# DIP_REFLOW_v1.net
KiCad netlist of a schematic drawn in EAGLE
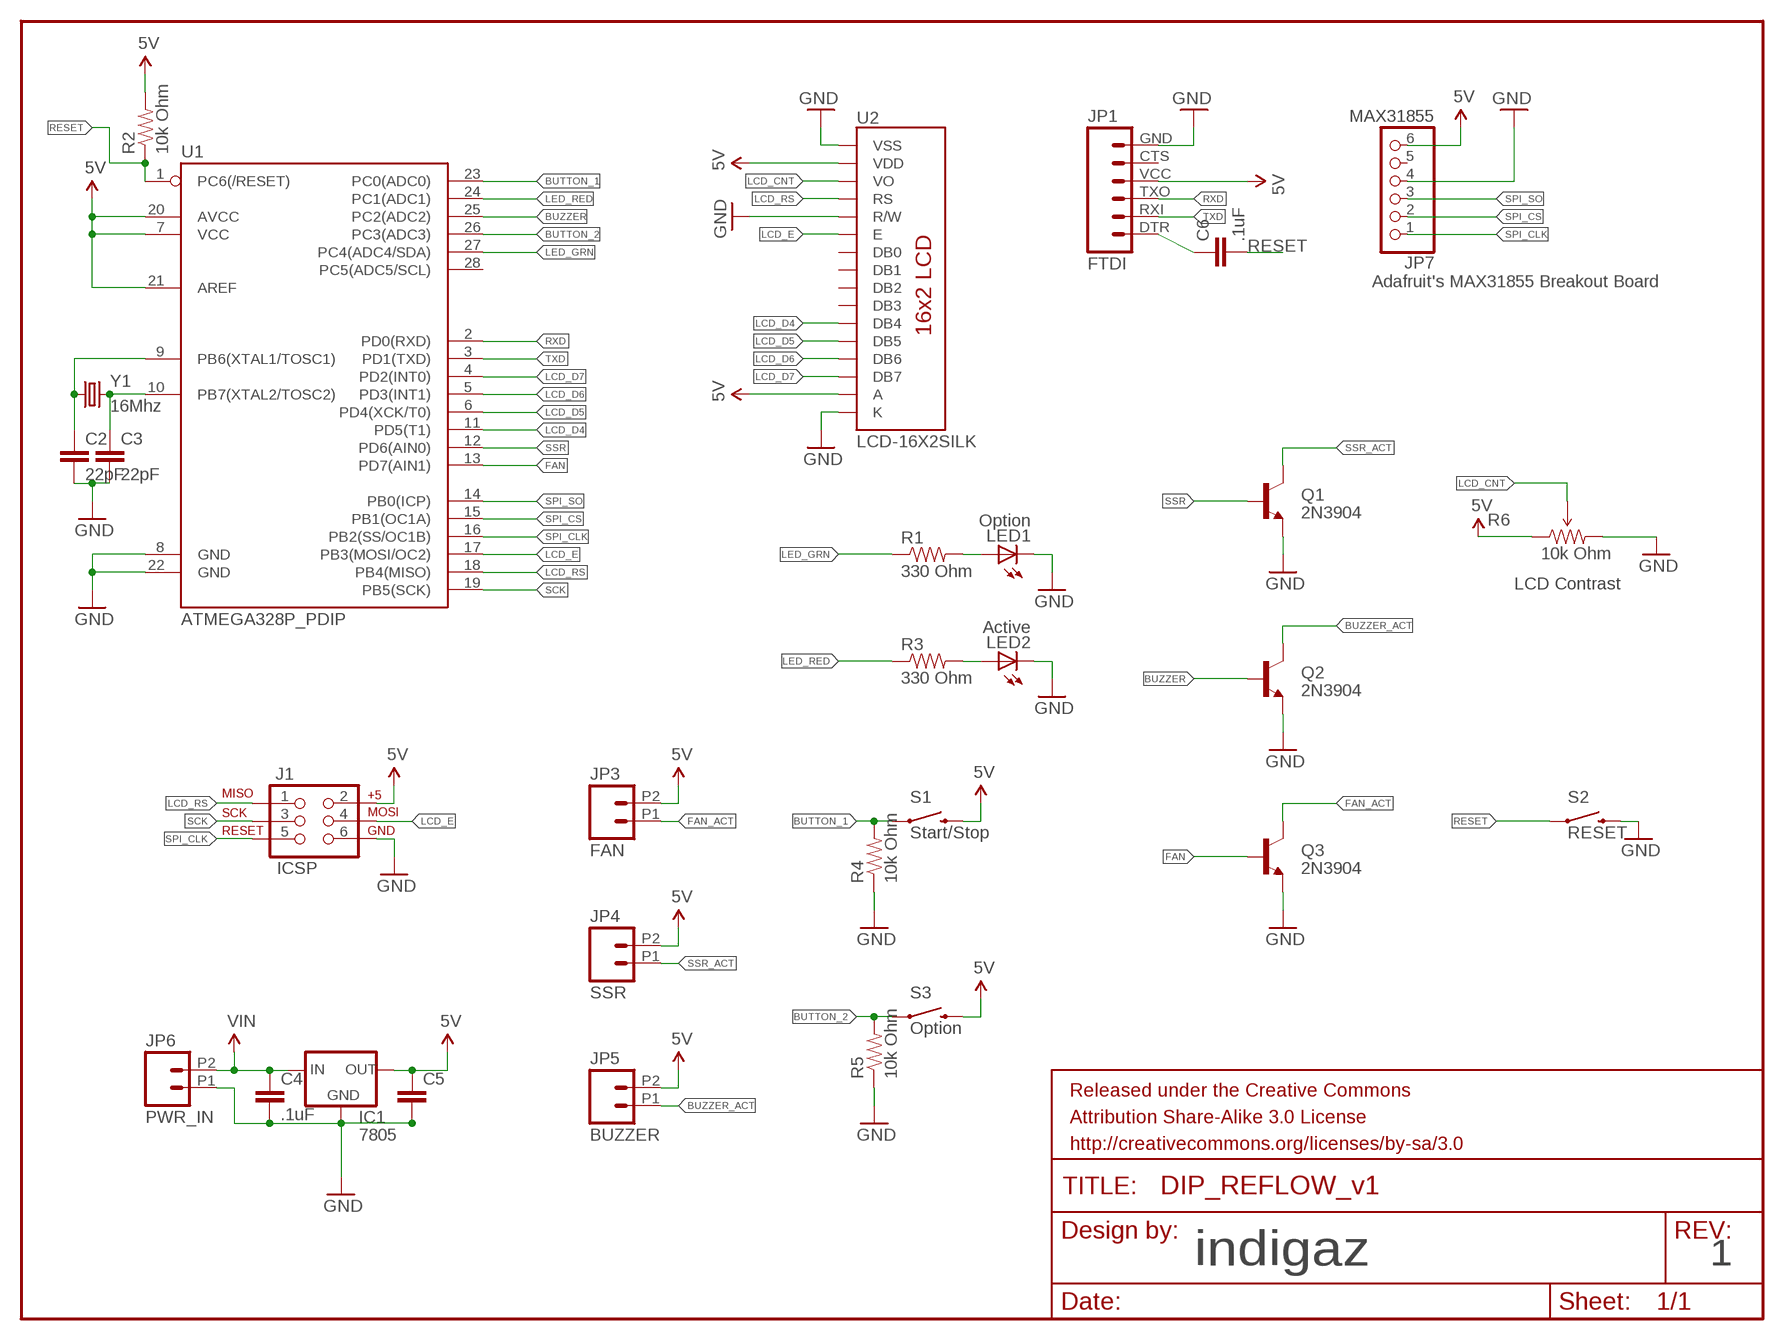
[diagram p0: schematic, sheet 1]

(export (version "E")
  (design (tool "Eeschema 10.0.6"))
  (components
    (comp (ref "C2")
      (value "22pF")
      (footprint "eagle-import:CAP-PTH-5MM")
      (libsource (lib "eagle-import") (part "CAPPTH1"))
    )
    (comp (ref "C3")
      (value "22pF")
      (footprint "eagle-import:CAP-PTH-5MM")
      (libsource (lib "eagle-import") (part "CAPPTH1"))
    )
    (comp (ref "C4")
      (value ".1uF")
      (footprint "eagle-import:CAP-PTH-5MM")
      (libsource (lib "eagle-import") (part "CAPPTH1"))
    )
    (comp (ref "C5")
      (value "CAPPTH1")
      (footprint "eagle-import:CAP-PTH-5MM")
      (libsource (lib "eagle-import") (part "CAPPTH1"))
    )
    (comp (ref "C6")
      (value ".1uF")
      (footprint "eagle-import:CAP-PTH-5MM")
      (libsource (lib "eagle-import") (part "CAPPTH1"))
    )
    (comp (ref "FRAME1")
      (value "FRAME-LETTER")
      (footprint "eagle-import:CREATIVE_COMMONS")
      (libsource (lib "eagle-import") (part "FRAME-LETTER"))
    )
    (comp (ref "IC1")
      (value "7805")
      (footprint "eagle-import:TO-220-ALT")
      (libsource (lib "eagle-import") (part "V_REG_78XX-TO-220"))
    )
    (comp (ref "J1")
      (value "ICSP")
      (footprint "eagle-import:2X3")
      (libsource (lib "eagle-import") (part "AVR_SPI_PRG_6PTH"))
    )
    (comp (ref "JP1")
      (value "FTDI")
      (footprint "eagle-import:FTDI_BASIC")
      (libsource (lib "eagle-import") (part "FTDI_BASICPTH"))
    )
    (comp (ref "JP3")
      (value "FAN")
      (footprint "eagle-import:1X02_2.54_SCREWTERM")
      (libsource (lib "eagle-import") (part "M022.54MM_SCREWTERM"))
    )
    (comp (ref "JP4")
      (value "SSR")
      (footprint "eagle-import:1X02_2.54_SCREWTERM")
      (libsource (lib "eagle-import") (part "M022.54MM_SCREWTERM"))
    )
    (comp (ref "JP5")
      (value "BUZZER")
      (footprint "eagle-import:1X02_2.54_SCREWTERM")
      (libsource (lib "eagle-import") (part "M022.54MM_SCREWTERM"))
    )
    (comp (ref "JP6")
      (value "PWR_IN")
      (footprint "eagle-import:1X02_2.54_SCREWTERM")
      (libsource (lib "eagle-import") (part "M022.54MM_SCREWTERM"))
    )
    (comp (ref "JP7")
      (value "MAX31855")
      (footprint "eagle-import:1X06")
      (libsource (lib "eagle-import") (part "PINHD-1X6"))
    )
    (comp (ref "LED1")
      (value "Option")
      (footprint "eagle-import:LED5MM")
      (libsource (lib "eagle-import") (part "LED5MM"))
    )
    (comp (ref "LED2")
      (value "Active")
      (footprint "eagle-import:LED5MM")
      (libsource (lib "eagle-import") (part "LED5MM"))
    )
    (comp (ref "Q1")
      (value "2N3904")
      (footprint "eagle-import:TO-92-AMMO")
      (libsource (lib "eagle-import") (part "TRANSISTOR_NPNTO-92-AMMO"))
    )
    (comp (ref "Q2")
      (value "2N3904")
      (footprint "eagle-import:TO-92-AMMO")
      (libsource (lib "eagle-import") (part "TRANSISTOR_NPNTO-92-AMMO"))
    )
    (comp (ref "Q3")
      (value "2N3904")
      (footprint "eagle-import:TO-92-AMMO")
      (libsource (lib "eagle-import") (part "TRANSISTOR_NPNTO-92-AMMO"))
    )
    (comp (ref "R1")
      (value "330 Ohm")
      (footprint "eagle-import:AXIAL-0.4")
      (libsource (lib "eagle-import") (part "RESISTORPTH-1/4W"))
    )
    (comp (ref "R2")
      (value "10k Ohm")
      (footprint "eagle-import:AXIAL-0.4")
      (libsource (lib "eagle-import") (part "RESISTORPTH-1/4W"))
    )
    (comp (ref "R3")
      (value "330 Ohm")
      (footprint "eagle-import:AXIAL-0.4")
      (libsource (lib "eagle-import") (part "RESISTORPTH-1/4W"))
    )
    (comp (ref "R4")
      (value "10k Ohm")
      (footprint "eagle-import:AXIAL-0.4")
      (libsource (lib "eagle-import") (part "RESISTORPTH-1/4W"))
    )
    (comp (ref "R5")
      (value "10k Ohm")
      (footprint "eagle-import:AXIAL-0.4")
      (libsource (lib "eagle-import") (part "RESISTORPTH-1/4W"))
    )
    (comp (ref "R6")
      (value "10k Ohm")
      (footprint "eagle-import:3386U")
      (libsource (lib "eagle-import") (part "TRIMPOT-PTH-KNOB"))
    )
    (comp (ref "S1")
      (value "Start/Stop")
      (footprint "eagle-import:TACTILE-PTH")
      (libsource (lib "eagle-import") (part "SWITCH-MOMENTARY-2PTH"))
    )
    (comp (ref "S2")
      (value "RESET")
      (footprint "eagle-import:TACTILE-PTH")
      (libsource (lib "eagle-import") (part "SWITCH-MOMENTARY-2PTH"))
    )
    (comp (ref "S3")
      (value "Option")
      (footprint "eagle-import:TACTILE-PTH")
      (libsource (lib "eagle-import") (part "SWITCH-MOMENTARY-2PTH"))
    )
    (comp (ref "U1")
      (value "ATMEGA328P_PDIP")
      (footprint "eagle-import:DIL28-3")
      (libsource (lib "eagle-import") (part "ATMEGA328P_PDIP"))
    )
    (comp (ref "U2")
      (value "LCD-16X2SILK")
      (footprint "eagle-import:LCD-16X2")
      (libsource (lib "eagle-import") (part "LCD-16X2SILK"))
    )
    (comp (ref "Y1")
      (value "16Mhz")
      (footprint "eagle-import:HC49US")
      (libsource (lib "eagle-import") (part "CRYSTALHC49US"))
    )
  )
  (nets
    (net (code "1") (name "5V") (class "Default")
      (node (ref "C5") (pin "1") (pinfunction "1_1") (pintype "passive"))
      (node (ref "IC1") (pin "OUT") (pinfunction "OUT_OUT") (pintype "output"))
      (node (ref "J1") (pin "2") (pinfunction "2_2") (pintype "passive"))
      (node (ref "JP1") (pin "VCC") (pinfunction "4_VCC") (pintype "passive"))
      (node (ref "JP3") (pin "P2") (pinfunction "2_P2") (pintype "passive"))
      (node (ref "JP4") (pin "P2") (pinfunction "2_P2") (pintype "passive"))
      (node (ref "JP5") (pin "P2") (pinfunction "2_P2") (pintype "passive"))
      (node (ref "JP7") (pin "6") (pinfunction "6_6") (pintype "passive"))
      (node (ref "R2") (pin "P$2") (pinfunction "2_P$2") (pintype "passive"))
      (node (ref "R6") (pin "1") (pinfunction "CCW_1") (pintype "passive"))
      (node (ref "S1") (pin "3") (pinfunction "2_3") (pintype "passive"))
      (node (ref "S3") (pin "3") (pinfunction "2_3") (pintype "passive"))
      (node (ref "U1") (pin "20") (pinfunction "AVCC_20") (pintype "bidirectional"))
      (node (ref "U1") (pin "21") (pinfunction "AREF_21") (pintype "bidirectional"))
      (node (ref "U1") (pin "7") (pinfunction "VCC_7") (pintype "bidirectional"))
      (node (ref "U2") (pin "15") (pinfunction "A_15") (pintype "power_in"))
      (node (ref "U2") (pin "2") (pinfunction "VDD_2") (pintype "power_in"))
    )
    (net (code "2") (name "BUTTON_1") (class "Default")
      (node (ref "R4") (pin "P$2") (pinfunction "2_P$2") (pintype "passive"))
      (node (ref "S1") (pin "1") (pinfunction "1_1") (pintype "passive"))
      (node (ref "U1") (pin "23") (pinfunction "PC0(ADC0)_23") (pintype "bidirectional"))
    )
    (net (code "3") (name "BUTTON_2") (class "Default")
      (node (ref "R5") (pin "P$2") (pinfunction "2_P$2") (pintype "passive"))
      (node (ref "S3") (pin "1") (pinfunction "1_1") (pintype "passive"))
      (node (ref "U1") (pin "26") (pinfunction "PC3(ADC3)_26") (pintype "bidirectional"))
    )
    (net (code "4") (name "BUZZER") (class "Default")
      (node (ref "Q2") (pin "2") (pinfunction "B_2") (pintype "passive"))
      (node (ref "U1") (pin "25") (pinfunction "PC2(ADC2)_25") (pintype "bidirectional"))
    )
    (net (code "5") (name "BUZZER_ACT") (class "Default")
      (node (ref "JP5") (pin "P1") (pinfunction "1_P1") (pintype "passive"))
      (node (ref "Q2") (pin "3") (pinfunction "C_3") (pintype "passive"))
    )
    (net (code "6") (name "FAN") (class "Default")
      (node (ref "Q3") (pin "2") (pinfunction "B_2") (pintype "passive"))
      (node (ref "U1") (pin "13") (pinfunction "PD7(AIN1)_13") (pintype "bidirectional"))
    )
    (net (code "7") (name "FAN_ACT") (class "Default")
      (node (ref "JP3") (pin "P1") (pinfunction "1_P1") (pintype "passive"))
      (node (ref "Q3") (pin "3") (pinfunction "C_3") (pintype "passive"))
    )
    (net (code "8") (name "GND") (class "Default")
      (node (ref "C2") (pin "2") (pinfunction "2_2") (pintype "passive"))
      (node (ref "C3") (pin "2") (pinfunction "2_2") (pintype "passive"))
      (node (ref "C4") (pin "2") (pinfunction "2_2") (pintype "passive"))
      (node (ref "C5") (pin "2") (pinfunction "2_2") (pintype "passive"))
      (node (ref "IC1") (pin "GND") (pinfunction "GND_GND") (pintype "input"))
      (node (ref "J1") (pin "6") (pinfunction "6_6") (pintype "passive"))
      (node (ref "JP1") (pin "GND") (pinfunction "6_GND") (pintype "passive"))
      (node (ref "JP6") (pin "P1") (pinfunction "1_P1") (pintype "passive"))
      (node (ref "JP7") (pin "4") (pinfunction "4_4") (pintype "passive"))
      (node (ref "LED1") (pin "K") (pinfunction "C_K") (pintype "passive"))
      (node (ref "LED2") (pin "K") (pinfunction "C_K") (pintype "passive"))
      (node (ref "Q1") (pin "1") (pinfunction "E_1") (pintype "passive"))
      (node (ref "Q2") (pin "1") (pinfunction "E_1") (pintype "passive"))
      (node (ref "Q3") (pin "1") (pinfunction "E_1") (pintype "passive"))
      (node (ref "R4") (pin "P$1") (pinfunction "1_P$1") (pintype "passive"))
      (node (ref "R5") (pin "P$1") (pinfunction "1_P$1") (pintype "passive"))
      (node (ref "R6") (pin "3") (pinfunction "CW_3") (pintype "passive"))
      (node (ref "S2") (pin "3") (pinfunction "2_3") (pintype "passive"))
      (node (ref "U1") (pin "22") (pinfunction "GND_22") (pintype "bidirectional"))
      (node (ref "U1") (pin "8") (pinfunction "GND_8") (pintype "bidirectional"))
      (node (ref "U2") (pin "1") (pinfunction "VSS_1") (pintype "power_in"))
      (node (ref "U2") (pin "16") (pinfunction "K_16") (pintype "power_in"))
      (node (ref "U2") (pin "5") (pinfunction "R/W_5") (pintype "input"))
    )
    (net (code "9") (name "LCD_CNT") (class "Default")
      (node (ref "R6") (pin "2") (pinfunction "WIPER_2") (pintype "passive"))
      (node (ref "U2") (pin "3") (pinfunction "VO_3") (pintype "bidirectional"))
    )
    (net (code "10") (name "LCD_D4") (class "Default")
      (node (ref "U1") (pin "11") (pinfunction "PD5(T1)_11") (pintype "bidirectional"))
      (node (ref "U2") (pin "11") (pinfunction "DB4_11") (pintype "bidirectional"))
    )
    (net (code "11") (name "LCD_D5") (class "Default")
      (node (ref "U1") (pin "6") (pinfunction "PD4(XCK/T0)_6") (pintype "bidirectional"))
      (node (ref "U2") (pin "12") (pinfunction "DB5_12") (pintype "bidirectional"))
    )
    (net (code "12") (name "LCD_D6") (class "Default")
      (node (ref "U1") (pin "5") (pinfunction "PD3(INT1)_5") (pintype "bidirectional"))
      (node (ref "U2") (pin "13") (pinfunction "DB6_13") (pintype "bidirectional"))
    )
    (net (code "13") (name "LCD_D7") (class "Default")
      (node (ref "U1") (pin "4") (pinfunction "PD2(INT0)_4") (pintype "bidirectional"))
      (node (ref "U2") (pin "14") (pinfunction "DB7_14") (pintype "bidirectional"))
    )
    (net (code "14") (name "LCD_E") (class "Default")
      (node (ref "J1") (pin "4") (pinfunction "4_4") (pintype "passive"))
      (node (ref "U1") (pin "17") (pinfunction "PB3(MOSI/OC2)_17") (pintype "bidirectional"))
      (node (ref "U2") (pin "6") (pinfunction "E_6") (pintype "input"))
    )
    (net (code "15") (name "LCD_RS") (class "Default")
      (node (ref "J1") (pin "1") (pinfunction "1_1") (pintype "passive"))
      (node (ref "U1") (pin "18") (pinfunction "PB4(MISO)_18") (pintype "bidirectional"))
      (node (ref "U2") (pin "4") (pinfunction "RS_4") (pintype "input"))
    )
    (net (code "16") (name "LED_GRN") (class "Default")
      (node (ref "R1") (pin "P$1") (pinfunction "1_P$1") (pintype "passive"))
      (node (ref "U1") (pin "27") (pinfunction "PC4(ADC4/SDA)_27") (pintype "bidirectional"))
    )
    (net (code "17") (name "LED_RED") (class "Default")
      (node (ref "R3") (pin "P$1") (pinfunction "1_P$1") (pintype "passive"))
      (node (ref "U1") (pin "24") (pinfunction "PC1(ADC1)_24") (pintype "bidirectional"))
    )
    (net (code "18") (name "Net-(JP1-1)") (class "Default")
      (node (ref "C6") (pin "1") (pinfunction "1_1") (pintype "passive"))
      (node (ref "JP1") (pin "DTR") (pinfunction "1_DTR") (pintype "passive"))
    )
    (net (code "19") (name "Net-(R1-2)") (class "Default")
      (node (ref "LED1") (pin "A") (pinfunction "A_A") (pintype "passive"))
      (node (ref "R1") (pin "P$2") (pinfunction "2_P$2") (pintype "passive"))
    )
    (net (code "20") (name "Net-(R3-2)") (class "Default")
      (node (ref "LED2") (pin "A") (pinfunction "A_A") (pintype "passive"))
      (node (ref "R3") (pin "P$2") (pinfunction "2_P$2") (pintype "passive"))
    )
    (net (code "21") (name "Net-(U1-PB6(XTAL1{slash}TOSC1))") (class "Default")
      (node (ref "C2") (pin "1") (pinfunction "1_1") (pintype "passive"))
      (node (ref "U1") (pin "9") (pinfunction "PB6(XTAL1/TOSC1)_9") (pintype "bidirectional"))
      (node (ref "Y1") (pin "1") (pinfunction "1_1") (pintype "passive"))
    )
    (net (code "22") (name "Net-(U1-PB7(XTAL2{slash}TOSC2))") (class "Default")
      (node (ref "C3") (pin "1") (pinfunction "1_1") (pintype "passive"))
      (node (ref "U1") (pin "10") (pinfunction "PB7(XTAL2/TOSC2)_10") (pintype "bidirectional"))
      (node (ref "Y1") (pin "2") (pinfunction "2_2") (pintype "passive"))
    )
    (net (code "23") (name "RESET") (class "Default")
      (node (ref "C6") (pin "2") (pinfunction "2_2") (pintype "passive"))
      (node (ref "R2") (pin "P$1") (pinfunction "1_P$1") (pintype "passive"))
      (node (ref "S2") (pin "1") (pinfunction "1_1") (pintype "passive"))
      (node (ref "U1") (pin "1") (pinfunction "PC6(/RESET)_1") (pintype "bidirectional"))
    )
    (net (code "24") (name "RXD") (class "Default")
      (node (ref "JP1") (pin "TXO") (pinfunction "3_TXO") (pintype "passive"))
      (node (ref "U1") (pin "2") (pinfunction "PD0(RXD)_2") (pintype "bidirectional"))
    )
    (net (code "25") (name "SCK") (class "Default")
      (node (ref "J1") (pin "3") (pinfunction "3_3") (pintype "passive"))
      (node (ref "U1") (pin "19") (pinfunction "PB5(SCK)_19") (pintype "bidirectional"))
    )
    (net (code "26") (name "SPI_CLK") (class "Default")
      (node (ref "J1") (pin "5") (pinfunction "5_5") (pintype "passive"))
      (node (ref "JP7") (pin "1") (pinfunction "1_1") (pintype "passive"))
      (node (ref "U1") (pin "16") (pinfunction "PB2(SS/OC1B)_16") (pintype "bidirectional"))
    )
    (net (code "27") (name "SPI_CS") (class "Default")
      (node (ref "JP7") (pin "2") (pinfunction "2_2") (pintype "passive"))
      (node (ref "U1") (pin "15") (pinfunction "PB1(OC1A)_15") (pintype "bidirectional"))
    )
    (net (code "28") (name "SPI_SO") (class "Default")
      (node (ref "JP7") (pin "3") (pinfunction "3_3") (pintype "passive"))
      (node (ref "U1") (pin "14") (pinfunction "PB0(ICP)_14") (pintype "bidirectional"))
    )
    (net (code "29") (name "SSR") (class "Default")
      (node (ref "Q1") (pin "2") (pinfunction "B_2") (pintype "passive"))
      (node (ref "U1") (pin "12") (pinfunction "PD6(AIN0)_12") (pintype "bidirectional"))
    )
    (net (code "30") (name "SSR_ACT") (class "Default")
      (node (ref "JP4") (pin "P1") (pinfunction "1_P1") (pintype "passive"))
      (node (ref "Q1") (pin "3") (pinfunction "C_3") (pintype "passive"))
    )
    (net (code "31") (name "TXD") (class "Default")
      (node (ref "JP1") (pin "RXI") (pinfunction "2_RXI") (pintype "passive"))
      (node (ref "U1") (pin "3") (pinfunction "PD1(TXD)_3") (pintype "bidirectional"))
    )
    (net (code "32") (name "VIN") (class "Default")
      (node (ref "C4") (pin "1") (pinfunction "1_1") (pintype "passive"))
      (node (ref "IC1") (pin "IN") (pinfunction "IN_IN") (pintype "input"))
      (node (ref "JP6") (pin "P2") (pinfunction "2_P2") (pintype "passive"))
    )
    (net (code "33") (name "unconnected-(JP1-5-PadCTS)") (class "Default")
      (node (ref "JP1") (pin "CTS") (pinfunction "5_CTS") (pintype "passive"))
    )
    (net (code "34") (name "unconnected-(JP7-Pad5)") (class "Default")
      (node (ref "JP7") (pin "5") (pinfunction "5_5") (pintype "passive"))
    )
    (net (code "35") (name "unconnected-(U1-PC5(ADC5{slash}SCL)-Pad28)") (class "Default")
      (node (ref "U1") (pin "28") (pinfunction "PC5(ADC5/SCL)_28") (pintype "bidirectional"))
    )
    (net (code "36") (name "unconnected-(U2-DB0-Pad7)") (class "Default")
      (node (ref "U2") (pin "7") (pinfunction "DB0_7") (pintype "bidirectional"))
    )
    (net (code "37") (name "unconnected-(U2-DB1-Pad8)") (class "Default")
      (node (ref "U2") (pin "8") (pinfunction "DB1_8") (pintype "bidirectional"))
    )
    (net (code "38") (name "unconnected-(U2-DB2-Pad9)") (class "Default")
      (node (ref "U2") (pin "9") (pinfunction "DB2_9") (pintype "bidirectional"))
    )
    (net (code "39") (name "unconnected-(U2-DB3-Pad10)") (class "Default")
      (node (ref "U2") (pin "10") (pinfunction "DB3_10") (pintype "bidirectional"))
    )
  )
)
